# RF.net
KiCad netlist of a schematic drawn in Altium Designer
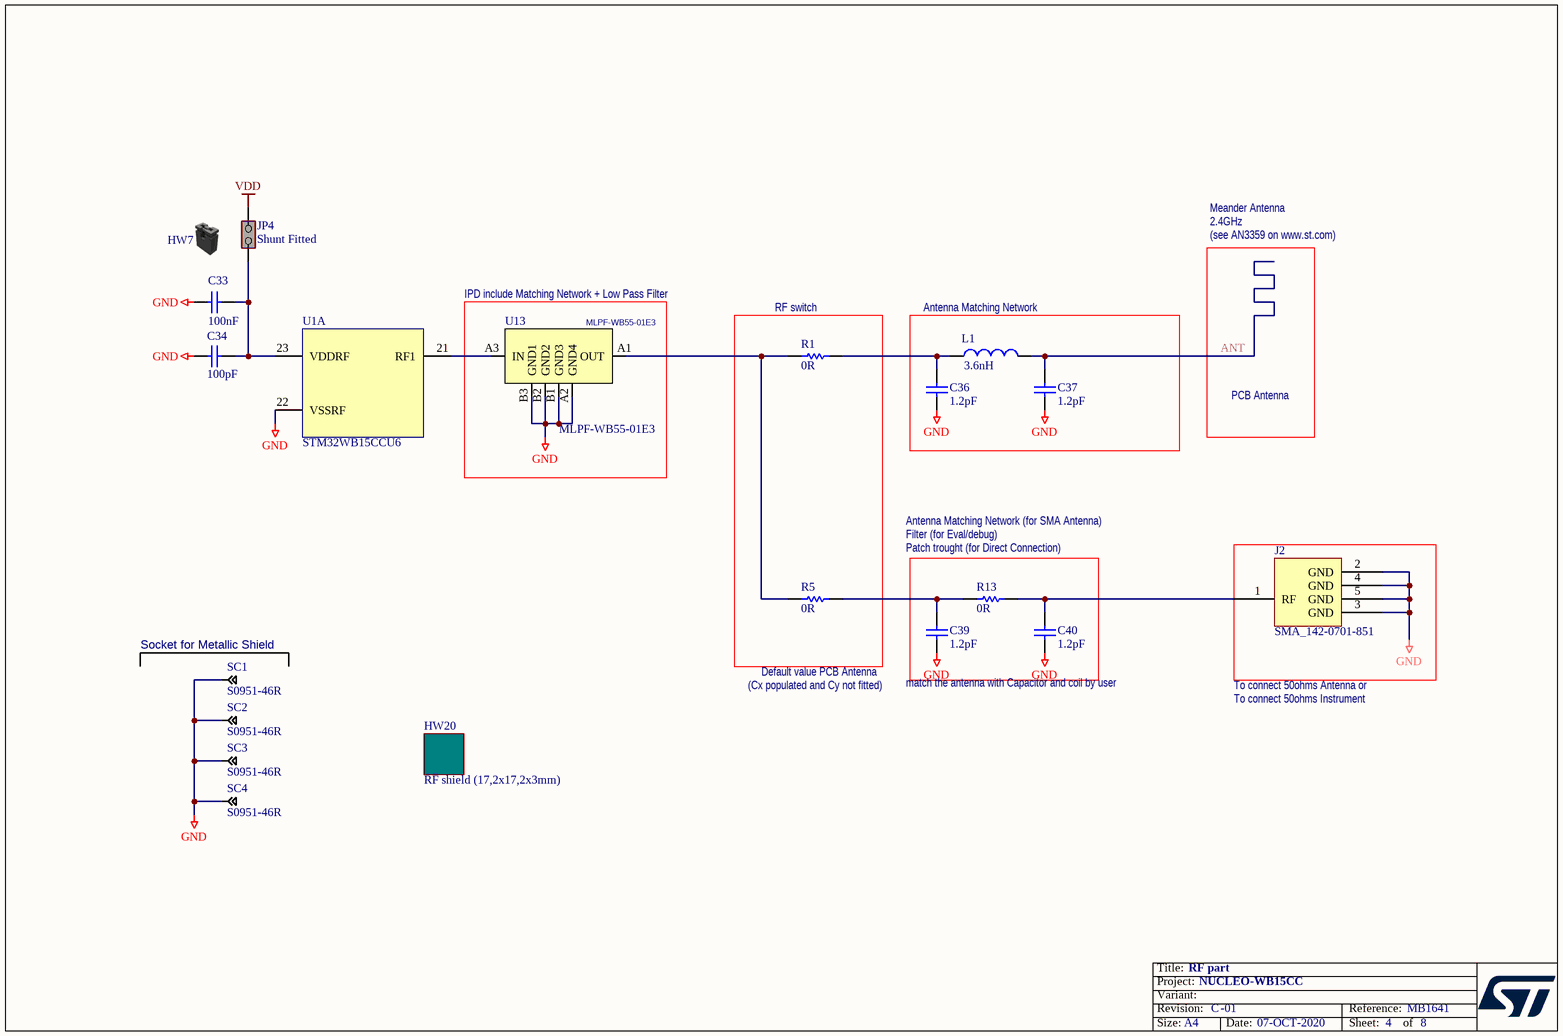
[diagram p0: RF.SchDoc]

(export (version "E")
  (design (tool "Eeschema 10.0.6"))
  (components
    (comp (ref "C33")
      (value "100nF")
      (footprint "C0402")
      (description "Capacitor, MLCC, 100nF, 16V, X7R, +/-10%, 0402, T=0.5mm")
      (fields
        (field (name "INTERNAL_PART_NUMBER") "MCD-00006")
        (field (name "MANUFACTURER_PART_NUMBER") "CC0402KRX7R7BB104")
      )
      (libsource (lib "MCD_PARTS_database") (part "Capacitor"))
    )
    (comp (ref "C34")
      (value "100pF")
      (footprint "C0402")
      (description "Capacitor,MLCC,100pF,50V,NPO,+/-5%,0402,T=0,5mm")
      (fields
        (field (name "INTERNAL_PART_NUMBER") "MCD-00205")
        (field (name "MANUFACTURER_PART_NUMBER") "CC0402JRNPO9BN101")
      )
      (libsource (lib "MCD_PARTS_database") (part "Capacitor"))
    )
    (comp (ref "C36")
      (value "1.2pF")
      (footprint "C0402")
      (description "Capacitor, High Q type for high frequency and high power, SMD, 1.2pF, 50V, 0,05pf, 0402")
      (fields
        (field (name "INTERNAL_PART_NUMBER") "MCD-02065")
        (field (name "MANUFACTURER_PART_NUMBER") "GJM1555C1H1R2WB01D")
      )
      (libsource (lib "MCD_PARTS_database") (part "Capacitor"))
    )
    (comp (ref "C37")
      (value "1.2pF")
      (footprint "C0402")
      (description "Capacitor, High Q type for high frequency and high power, SMD, 1.2pF, 50V, 0,05pf, 0402")
      (fields
        (field (name "INTERNAL_PART_NUMBER") "MCD-02065")
        (field (name "MANUFACTURER_PART_NUMBER") "GJM1555C1H1R2WB01D")
      )
      (libsource (lib "MCD_PARTS_database") (part "Capacitor"))
    )
    (comp (ref "C39")
      (value "1.2pF")
      (footprint "C0402")
      (description "Capacitor, High Q type for high frequency and high power, SMD, 1.2pF, 50V, 0,05pf, 0402")
      (fields
        (field (name "INTERNAL_PART_NUMBER") "MCD-02065")
        (field (name "MANUFACTURER_PART_NUMBER") "GJM1555C1H1R2WB01D")
      )
      (libsource (lib "MCD_PARTS_database") (part "Capacitor"))
    )
    (comp (ref "C40")
      (value "1.2pF")
      (footprint "C0402")
      (description "Capacitor, High Q type for high frequency and high power, SMD, 1.2pF, 50V, 0,05pf, 0402")
      (fields
        (field (name "INTERNAL_PART_NUMBER") "MCD-02065")
        (field (name "MANUFACTURER_PART_NUMBER") "GJM1555C1H1R2WB01D")
      )
      (libsource (lib "MCD_PARTS_database") (part "Capacitor"))
    )
    (comp (ref "HW7")
      (value "Shunt Black 2.54mm")
      (description "SHUNT 2.54mm BLACK")
      (fields
        (field (name "INTERNAL_PART_NUMBER") "MCD-00043")
        (field (name "MANUFACTURER_PART_NUMBER") "SNT-100-BK-G")
      )
      (libsource (lib "MCD_PARTS_database") (part "Shunt Black 2.54mm"))
    )
    (comp (ref "HW20")
      (value "RF shield (17,2x17,2x3mm)")
      (footprint "SHIELD_RF_ST-CUSTOM_17P2X17P2_H3")
      (description "RF shield (17,2x17,2x3mm), Brass with Sn finishing, Sheet tickness : 0,2mm")
      (fields (field (name "INTERNAL_PART_NUMBER") "MCD-02088") (field (name "Comment") "Daughter_Board"))
      (libsource (lib "MCD_PARTS_database") (part "Daughter_Board"))
    )
    (comp (ref "J2")
      (value "SMA_142-0701-851")
      (footprint "CON_SMA-RF_CINCH_142-0701-851")
      (description "RF SMA connector PCB edge")
      (fields
        (field (name "INTERNAL_PART_NUMBER") "MCD-02072")
        (field (name "MANUFACTURER_PART_NUMBER") "142-0701-851")
      )
      (libsource (lib "MCD_PARTS_database") (part "SMA-J-P-H-ST-EM1"))
    )
    (comp (ref "JP4")
      (value "Shunt Fitted")
      (footprint "CON_SAMTEC_TSW-102-07-G-S")
      (description "Header, 2x1, 2,54mm, VR, TH, Height 5.84mm/2.54mm - Shunt Fitted by default")
      (fields
        (field (name "INTERNAL_PART_NUMBER") "MCD-00683")
        (field (name "MANUFACTURER_PART_NUMBER") "TSW-102-07-G-S")
      )
      (libsource (lib "MCD_PARTS_database") (part "Jumper_Header 2x1 Fitted"))
    )
    (comp (ref "L1")
      (value "3.6nH")
      (footprint "IND_0402_MURATA_LGQ15HS02_H0P5")
      (description "Inductor, LQG15H, 3.6nH, +-0.3nH 0402")
      (fields
        (field (name "INTERNAL_PART_NUMBER") "MCD-01461")
        (field (name "MANUFACTURER_PART_NUMBER") "LQG15HS3N6S02")
      )
      (libsource (lib "MCD_PARTS_database") (part "Inductor"))
    )
    (comp (ref "R1")
      (value "0R")
      (footprint "R0402")
      (description "Resistor,0R,0402,5%,1/16W")
      (fields (field (name "INTERNAL_PART_NUMBER") "MCD-00052") (field (name "MANUFACTURER") "YAGEO"))
      (libsource (lib "MCD_PARTS_database") (part "Resistor"))
    )
    (comp (ref "R5")
      (value "0R")
      (footprint "R0402")
      (description "Resistor,0R,0402,5%,1/16W")
      (fields (field (name "INTERNAL_PART_NUMBER") "MCD-00052") (field (name "MANUFACTURER") "YAGEO"))
      (libsource (lib "MCD_PARTS_database") (part "Resistor"))
    )
    (comp (ref "R13")
      (value "0R")
      (footprint "R0402")
      (description "Resistor,0R,0402,5%,1/16W")
      (fields (field (name "INTERNAL_PART_NUMBER") "MCD-00052") (field (name "MANUFACTURER") "YAGEO"))
      (libsource (lib "MCD_PARTS_database") (part "Resistor"))
    )
    (comp (ref "SC1")
      (value "S0951-46R")
      (footprint "CLIP_HARWIN_S0951-46R")
      (description "shield clip Harwin S0951-46R to fix RF shielded cavity")
      (fields (field (name "INTERNAL_PART_NUMBER") "MCD-01587") (field (name "MANUFACTURER") "HARWIN"))
      (libsource (lib "MCD_PARTS_database") (part "Shield-clip_S0951-46R"))
    )
    (comp (ref "SC2")
      (value "S0951-46R")
      (footprint "CLIP_HARWIN_S0951-46R")
      (description "shield clip Harwin S0951-46R to fix RF shielded cavity")
      (fields (field (name "INTERNAL_PART_NUMBER") "MCD-01587") (field (name "MANUFACTURER") "HARWIN"))
      (libsource (lib "MCD_PARTS_database") (part "Shield-clip_S0951-46R"))
    )
    (comp (ref "SC3")
      (value "S0951-46R")
      (footprint "CLIP_HARWIN_S0951-46R")
      (description "shield clip Harwin S0951-46R to fix RF shielded cavity")
      (fields (field (name "INTERNAL_PART_NUMBER") "MCD-01587") (field (name "MANUFACTURER") "HARWIN"))
      (libsource (lib "MCD_PARTS_database") (part "Shield-clip_S0951-46R"))
    )
    (comp (ref "SC4")
      (value "S0951-46R")
      (footprint "CLIP_HARWIN_S0951-46R")
      (description "shield clip Harwin S0951-46R to fix RF shielded cavity")
      (fields (field (name "INTERNAL_PART_NUMBER") "MCD-01587") (field (name "MANUFACTURER") "HARWIN"))
      (libsource (lib "MCD_PARTS_database") (part "Shield-clip_S0951-46R"))
    )
    (comp (ref "U1")
      (value "STM32WB15CCU6")
      (footprint "ICC_UFQFPN48-EPAD_7X7_H0P55_P050")
      (fields
        (field (name "INTERNAL_PART_NUMBER") "MCD-02058")
        (field (name "MANUFACTURER") "STMICROELECTRONICS")
        (field (name "Comment") "STM32WB15_QFN48")
      )
      (libsource (lib "MCD_PARTS_database") (part "STM32WB15_QFN48"))
    )
    (comp (ref "U13")
      (value "MLPF-WB55-01E3")
      (footprint "ICC_BUMPLESS-CSP6_AN2348-FLIP-CHIP_1X1P60_P050-P0587")
      (description "2.4 GHz low pass filter matched to STM32WBx5Cx/Rx")
      (fields
        (field (name "INTERNAL_PART_NUMBER") "MCD-02059")
        (field (name "ALTIUM_VALUE") "MLPF-WB55-01E3")
        (field (name "MANUFACTURER") "STMICROELECTRONICS")
      )
      (libsource (lib "MCD_PARTS_database") (part "MLPF-WB55-01E3"))
    )
  )
  (nets
    (net (code "1") (name "/ANT") (class "Default")
      (node (ref "C37") (pin "2") (pinfunction "2_2") (pintype "passive"))
      (node (ref "L1") (pin "2") (pinfunction "2_2") (pintype "passive"))
    )
    (net (code "2") (name "GND") (class "Default")
      (node (ref "C33") (pin "1") (pinfunction "1_1") (pintype "passive"))
      (node (ref "C34") (pin "1") (pinfunction "1_1") (pintype "passive"))
      (node (ref "C36") (pin "1") (pinfunction "1_1") (pintype "passive"))
      (node (ref "C37") (pin "1") (pinfunction "1_1") (pintype "passive"))
      (node (ref "C39") (pin "1") (pinfunction "1_1") (pintype "passive"))
      (node (ref "C40") (pin "1") (pinfunction "1_1") (pintype "passive"))
      (node (ref "J2") (pin "2") (pinfunction "GND_2") (pintype "passive"))
      (node (ref "J2") (pin "3") (pinfunction "GND_3") (pintype "passive"))
      (node (ref "J2") (pin "4") (pinfunction "GND_4") (pintype "passive"))
      (node (ref "J2") (pin "5") (pinfunction "GND_5") (pintype "passive"))
      (node (ref "SC1") (pin "1") (pinfunction "1_1") (pintype "passive"))
      (node (ref "SC2") (pin "1") (pinfunction "1_1") (pintype "passive"))
      (node (ref "SC3") (pin "1") (pinfunction "1_1") (pintype "passive"))
      (node (ref "SC4") (pin "1") (pinfunction "1_1") (pintype "passive"))
      (node (ref "U1") (pin "22") (pinfunction "VSSRF_22") (pintype "passive"))
      (node (ref "U13") (pin "A2") (pinfunction "GND4_A2") (pintype "passive"))
      (node (ref "U13") (pin "B1") (pinfunction "GND3_B1") (pintype "passive"))
      (node (ref "U13") (pin "B2") (pinfunction "GND2_B2") (pintype "passive"))
      (node (ref "U13") (pin "B3") (pinfunction "GND1_B3") (pintype "passive"))
    )
    (net (code "3") (name "Net-(C36-Pad2)") (class "Default")
      (node (ref "C36") (pin "2") (pinfunction "2_2") (pintype "passive"))
      (node (ref "L1") (pin "1") (pinfunction "1_1") (pintype "passive"))
      (node (ref "R1") (pin "2") (pinfunction "2_2") (pintype "passive"))
    )
    (net (code "4") (name "Net-(C39-Pad2)") (class "Default")
      (node (ref "C39") (pin "2") (pinfunction "2_2") (pintype "passive"))
      (node (ref "R13") (pin "1") (pinfunction "1_1") (pintype "passive"))
      (node (ref "R5") (pin "2") (pinfunction "2_2") (pintype "passive"))
    )
    (net (code "5") (name "Net-(J2-RF)") (class "Default")
      (node (ref "C40") (pin "2") (pinfunction "2_2") (pintype "passive"))
      (node (ref "J2") (pin "1") (pinfunction "RF_1") (pintype "passive"))
      (node (ref "R13") (pin "2") (pinfunction "2_2") (pintype "passive"))
    )
    (net (code "6") (name "Net-(JP4-NO)") (class "Default")
      (node (ref "C33") (pin "2") (pinfunction "2_2") (pintype "passive"))
      (node (ref "C34") (pin "2") (pinfunction "2_2") (pintype "passive"))
      (node (ref "JP4") (pin "2") (pinfunction "NO_2") (pintype "passive"))
      (node (ref "U1") (pin "23") (pinfunction "VDDRF_23") (pintype "passive"))
    )
    (net (code "7") (name "Net-(U13-IN)") (class "Default")
      (node (ref "U1") (pin "21") (pinfunction "RF1_21") (pintype "passive"))
      (node (ref "U13") (pin "A3") (pinfunction "IN_A3") (pintype "passive"))
    )
    (net (code "8") (name "Net-(U13-OUT)") (class "Default")
      (node (ref "R1") (pin "1") (pinfunction "1_1") (pintype "passive"))
      (node (ref "R5") (pin "1") (pinfunction "1_1") (pintype "passive"))
      (node (ref "U13") (pin "A1") (pinfunction "OUT_A1") (pintype "passive"))
    )
    (net (code "9") (name "VDD") (class "Default")
      (node (ref "JP4") (pin "1") (pinfunction "COMMON_1") (pintype "passive"))
    )
  )
)
